# PCD.net
KiCad netlist of a schematic drawn in EAGLE
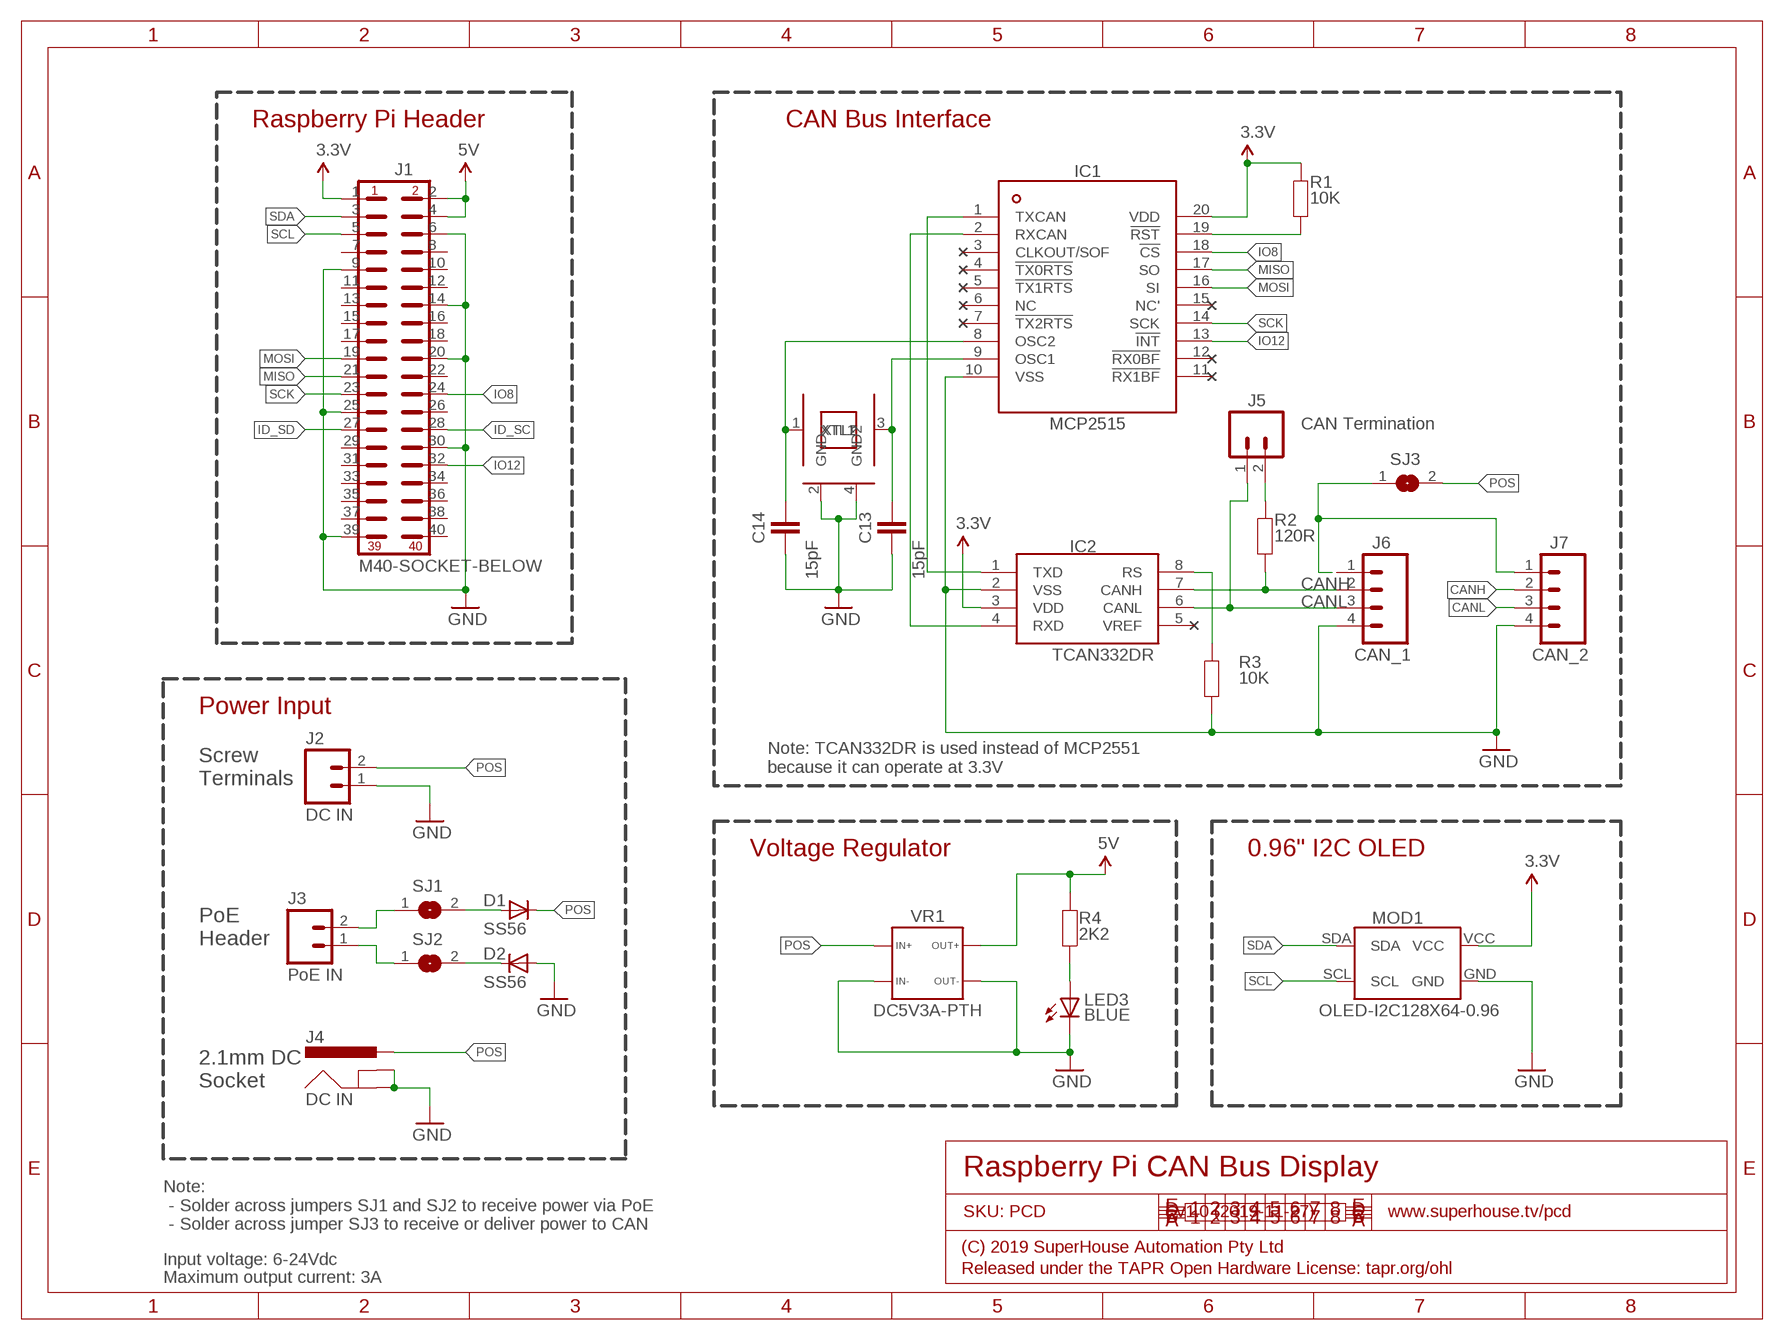
[diagram p0: schematic, sheet 1]

(export (version "E")
  (design (tool "Eeschema 10.0.6"))
  (components
    (comp (ref "C13")
      (value "15pF")
      (footprint "eagle-import:C0603")
      (libsource (lib "eagle-import") (part "CAP0603"))
    )
    (comp (ref "C14")
      (value "15pF")
      (footprint "eagle-import:C0603")
      (libsource (lib "eagle-import") (part "CAP0603"))
    )
    (comp (ref "D1")
      (value "SS56")
      (footprint "eagle-import:SMA-DIODE")
      (libsource (lib "eagle-import") (part "DIODESMA"))
    )
    (comp (ref "D2")
      (value "SS56")
      (footprint "eagle-import:SMA-DIODE")
      (libsource (lib "eagle-import") (part "DIODESMA"))
    )
    (comp (ref "IC1")
      (value "MCP2515")
      (footprint "eagle-import:TSSOP20")
      (libsource (lib "eagle-import") (part "MCP2515"))
    )
    (comp (ref "IC2")
      (value "TCAN332DR")
      (footprint "eagle-import:SO08")
      (libsource (lib "eagle-import") (part "MCP2551"))
    )
    (comp (ref "J1")
      (value "M40-SOCKET-BELOW")
      (footprint "eagle-import:2X20-S-BELOW")
      (libsource (lib "eagle-import") (part "M40-SOCKET-BELOW"))
    )
    (comp (ref "J2")
      (value "DC IN")
      (footprint "eagle-import:SCREWTERMINAL-3.5MM-2")
      (libsource (lib "eagle-import") (part "M02-SCREW-3.5MM"))
    )
    (comp (ref "J3")
      (value "PoE IN")
      (footprint "eagle-import:1X02-S-BELOW")
      (libsource (lib "eagle-import") (part "M02-SOCKET-BELOW"))
    )
    (comp (ref "J4")
      (value "DC IN")
      (footprint "eagle-import:POWER_JACK_SLOTS")
      (libsource (lib "eagle-import") (part "POWER_JACK-SLOTS"))
    )
    (comp (ref "J5")
      (value "CAN Termination")
      (footprint "eagle-import:1X02-P")
      (libsource (lib "eagle-import") (part "M02-PIN"))
    )
    (comp (ref "J6")
      (value "CAN_1")
      (footprint "eagle-import:1X04-P")
      (libsource (lib "eagle-import") (part "M04-PIN"))
    )
    (comp (ref "J7")
      (value "CAN_2")
      (footprint "eagle-import:1X04-P")
      (libsource (lib "eagle-import") (part "M04-PIN"))
    )
    (comp (ref "LED3")
      (value "BLUE")
      (footprint "eagle-import:LED-0603")
      (libsource (lib "eagle-import") (part "LED0603"))
    )
    (comp (ref "MOD1")
      (value "OLED-I2C128X64-0.96")
      (footprint "eagle-import:OLED-128X64-0.96")
      (libsource (lib "eagle-import") (part "OLED-I2C128X64-0.96"))
    )
    (comp (ref "R1")
      (value "10K")
      (footprint "eagle-import:R0603")
      (libsource (lib "eagle-import") (part "RESISTOR0603"))
    )
    (comp (ref "R2")
      (value "120R")
      (footprint "eagle-import:R0603")
      (libsource (lib "eagle-import") (part "RESISTOR0603"))
    )
    (comp (ref "R3")
      (value "10K")
      (footprint "eagle-import:R0603")
      (libsource (lib "eagle-import") (part "RESISTOR0603"))
    )
    (comp (ref "R4")
      (value "2K2")
      (footprint "eagle-import:R0603")
      (libsource (lib "eagle-import") (part "RESISTOR0603"))
    )
    (comp (ref "SJ1")
      (value "SJN")
      (footprint "eagle-import:SJ")
      (libsource (lib "eagle-import") (part "SJN"))
    )
    (comp (ref "SJ2")
      (value "SJN")
      (footprint "eagle-import:SJ")
      (libsource (lib "eagle-import") (part "SJN"))
    )
    (comp (ref "SJ3")
      (value "SJN")
      (footprint "eagle-import:SJ")
      (libsource (lib "eagle-import") (part "SJN"))
    )
    (comp (ref "VR1")
      (value "DC5V3A-PTH")
      (footprint "eagle-import:DC5V3A-PTH")
      (libsource (lib "eagle-import") (part "DC5V3A-PTH"))
    )
    (comp (ref "XTL3")
      (value "16MHz")
      (footprint "eagle-import:CRYSTAL-SMD-3X2")
      (libsource (lib "eagle-import") (part "CRYSTAL-GND3X2"))
    )
  )
  (nets
    (net (code "1") (name "3.3V") (class "Default")
      (node (ref "IC1") (pin "20") (pinfunction "VDD_20") (pintype "bidirectional"))
      (node (ref "IC2") (pin "3") (pinfunction "VDD_3") (pintype "bidirectional"))
      (node (ref "J1") (pin "1") (pinfunction "1_1") (pintype "passive"))
      (node (ref "MOD1") (pin "VCC") (pinfunction "VCC_VCC") (pintype "bidirectional"))
      (node (ref "R1") (pin "2") (pinfunction "2_2") (pintype "passive"))
    )
    (net (code "2") (name "5V") (class "Default")
      (node (ref "J1") (pin "2") (pinfunction "2_2") (pintype "passive"))
      (node (ref "J1") (pin "4") (pinfunction "4_4") (pintype "passive"))
      (node (ref "R4") (pin "1") (pinfunction "1_1") (pintype "passive"))
      (node (ref "VR1") (pin "3A") (pinfunction "3_3A") (pintype "bidirectional"))
      (node (ref "VR1") (pin "3B") (pinfunction "3_3B") (pintype "bidirectional"))
    )
    (net (code "3") (name "CANH") (class "Default")
      (node (ref "IC2") (pin "7") (pinfunction "CANH_7") (pintype "bidirectional"))
      (node (ref "J6") (pin "2") (pinfunction "2_2") (pintype "passive"))
      (node (ref "J7") (pin "2") (pinfunction "2_2") (pintype "passive"))
      (node (ref "R2") (pin "1") (pinfunction "1_1") (pintype "passive"))
    )
    (net (code "4") (name "CANL") (class "Default")
      (node (ref "IC2") (pin "6") (pinfunction "CANL_6") (pintype "bidirectional"))
      (node (ref "J5") (pin "1") (pinfunction "1_1") (pintype "passive"))
      (node (ref "J6") (pin "3") (pinfunction "3_3") (pintype "passive"))
      (node (ref "J7") (pin "3") (pinfunction "3_3") (pintype "passive"))
    )
    (net (code "5") (name "GND") (class "Default")
      (node (ref "C13") (pin "1") (pinfunction "1_1") (pintype "passive"))
      (node (ref "C14") (pin "1") (pinfunction "1_1") (pintype "passive"))
      (node (ref "D2") (pin "A") (pinfunction "A_A") (pintype "passive"))
      (node (ref "IC1") (pin "10") (pinfunction "VSS_10") (pintype "bidirectional"))
      (node (ref "IC2") (pin "2") (pinfunction "VSS_2") (pintype "bidirectional"))
      (node (ref "J1") (pin "14") (pinfunction "14_14") (pintype "passive"))
      (node (ref "J1") (pin "20") (pinfunction "20_20") (pintype "passive"))
      (node (ref "J1") (pin "25") (pinfunction "25_25") (pintype "passive"))
      (node (ref "J1") (pin "30") (pinfunction "30_30") (pintype "passive"))
      (node (ref "J1") (pin "39") (pinfunction "39_39") (pintype "passive"))
      (node (ref "J1") (pin "6") (pinfunction "6_6") (pintype "passive"))
      (node (ref "J1") (pin "9") (pinfunction "9_9") (pintype "passive"))
      (node (ref "J2") (pin "1") (pinfunction "1_1") (pintype "passive"))
      (node (ref "J4") (pin "GND") (pinfunction "GND_GND") (pintype "bidirectional"))
      (node (ref "J4") (pin "GNDBREAK") (pinfunction "GNDBREAK_GNDBREAK") (pintype "bidirectional"))
      (node (ref "J6") (pin "4") (pinfunction "4_4") (pintype "passive"))
      (node (ref "J7") (pin "4") (pinfunction "4_4") (pintype "passive"))
      (node (ref "LED3") (pin "C") (pinfunction "C_C") (pintype "passive"))
      (node (ref "MOD1") (pin "GND") (pinfunction "GND_GND") (pintype "bidirectional"))
      (node (ref "R3") (pin "1") (pinfunction "1_1") (pintype "passive"))
      (node (ref "VR1") (pin "1A") (pinfunction "1_1A") (pintype "bidirectional"))
      (node (ref "VR1") (pin "1B") (pinfunction "1_1B") (pintype "bidirectional"))
      (node (ref "VR1") (pin "4A") (pinfunction "4_4A") (pintype "bidirectional"))
      (node (ref "VR1") (pin "4B") (pinfunction "4_4B") (pintype "bidirectional"))
      (node (ref "XTL3") (pin "2") (pinfunction "GND_2") (pintype "bidirectional"))
      (node (ref "XTL3") (pin "4") (pinfunction "GND2_4") (pintype "bidirectional"))
    )
    (net (code "6") (name "ID_SC") (class "Default")
      (node (ref "J1") (pin "28") (pinfunction "28_28") (pintype "passive"))
    )
    (net (code "7") (name "ID_SD") (class "Default")
      (node (ref "J1") (pin "27") (pinfunction "27_27") (pintype "passive"))
    )
    (net (code "8") (name "IO8") (class "Default")
      (node (ref "IC1") (pin "18") (pinfunction "~{CS}_18") (pintype "bidirectional"))
      (node (ref "J1") (pin "24") (pinfunction "24_24") (pintype "passive"))
    )
    (net (code "9") (name "IO12") (class "Default")
      (node (ref "IC1") (pin "13") (pinfunction "~{INT}_13") (pintype "bidirectional"))
      (node (ref "J1") (pin "32") (pinfunction "32_32") (pintype "passive"))
    )
    (net (code "10") (name "MISO") (class "Default")
      (node (ref "IC1") (pin "17") (pinfunction "SO_17") (pintype "bidirectional"))
      (node (ref "J1") (pin "21") (pinfunction "21_21") (pintype "passive"))
    )
    (net (code "11") (name "MOSI") (class "Default")
      (node (ref "IC1") (pin "16") (pinfunction "SI_16") (pintype "bidirectional"))
      (node (ref "J1") (pin "19") (pinfunction "19_19") (pintype "passive"))
    )
    (net (code "12") (name "Net-(D1-PadA)") (class "Default")
      (node (ref "D1") (pin "A") (pinfunction "A_A") (pintype "passive"))
      (node (ref "SJ1") (pin "2") (pinfunction "2_2") (pintype "passive"))
    )
    (net (code "13") (name "Net-(D2-PadC)") (class "Default")
      (node (ref "D2") (pin "C") (pinfunction "C_C") (pintype "passive"))
      (node (ref "SJ2") (pin "2") (pinfunction "2_2") (pintype "passive"))
    )
    (net (code "14") (name "Net-(IC1-OSC1)") (class "Default")
      (node (ref "C13") (pin "2") (pinfunction "2_2") (pintype "passive"))
      (node (ref "IC1") (pin "9") (pinfunction "OSC1_9") (pintype "bidirectional"))
      (node (ref "XTL3") (pin "3") (pinfunction "XTL2_3") (pintype "bidirectional"))
    )
    (net (code "15") (name "Net-(IC1-OSC2)") (class "Default")
      (node (ref "C14") (pin "2") (pinfunction "2_2") (pintype "passive"))
      (node (ref "IC1") (pin "8") (pinfunction "OSC2_8") (pintype "bidirectional"))
      (node (ref "XTL3") (pin "1") (pinfunction "XTL1_1") (pintype "bidirectional"))
    )
    (net (code "16") (name "Net-(IC1-RXCAN)") (class "Default")
      (node (ref "IC1") (pin "2") (pinfunction "RXCAN_2") (pintype "bidirectional"))
      (node (ref "IC2") (pin "4") (pinfunction "RXD_4") (pintype "bidirectional"))
    )
    (net (code "17") (name "Net-(IC1-TXCAN)") (class "Default")
      (node (ref "IC1") (pin "1") (pinfunction "TXCAN_1") (pintype "bidirectional"))
      (node (ref "IC2") (pin "1") (pinfunction "TXD_1") (pintype "bidirectional"))
    )
    (net (code "18") (name "Net-(IC1-~{RST})") (class "Default")
      (node (ref "IC1") (pin "19") (pinfunction "~{RST}_19") (pintype "bidirectional"))
      (node (ref "R1") (pin "1") (pinfunction "1_1") (pintype "passive"))
    )
    (net (code "19") (name "Net-(IC2-RS)") (class "Default")
      (node (ref "IC2") (pin "8") (pinfunction "RS_8") (pintype "bidirectional"))
      (node (ref "R3") (pin "2") (pinfunction "2_2") (pintype "passive"))
    )
    (net (code "20") (name "Net-(J3-Pad1)") (class "Default")
      (node (ref "J3") (pin "1") (pinfunction "1_1") (pintype "passive"))
      (node (ref "SJ2") (pin "1") (pinfunction "1_1") (pintype "passive"))
    )
    (net (code "21") (name "Net-(J3-Pad2)") (class "Default")
      (node (ref "J3") (pin "2") (pinfunction "2_2") (pintype "passive"))
      (node (ref "SJ1") (pin "1") (pinfunction "1_1") (pintype "passive"))
    )
    (net (code "22") (name "Net-(J5-Pad2)") (class "Default")
      (node (ref "J5") (pin "2") (pinfunction "2_2") (pintype "passive"))
      (node (ref "R2") (pin "2") (pinfunction "2_2") (pintype "passive"))
    )
    (net (code "23") (name "Net-(J6-Pad1)") (class "Default")
      (node (ref "J6") (pin "1") (pinfunction "1_1") (pintype "passive"))
      (node (ref "J7") (pin "1") (pinfunction "1_1") (pintype "passive"))
      (node (ref "SJ3") (pin "1") (pinfunction "1_1") (pintype "passive"))
    )
    (net (code "24") (name "Net-(LED3-PadA)") (class "Default")
      (node (ref "LED3") (pin "A") (pinfunction "A_A") (pintype "passive"))
      (node (ref "R4") (pin "2") (pinfunction "2_2") (pintype "passive"))
    )
    (net (code "25") (name "POS") (class "Default")
      (node (ref "D1") (pin "C") (pinfunction "C_C") (pintype "passive"))
      (node (ref "J2") (pin "2") (pinfunction "2_2") (pintype "passive"))
      (node (ref "J4") (pin "PWR") (pinfunction "PWR_PWR") (pintype "bidirectional"))
      (node (ref "SJ3") (pin "2") (pinfunction "2_2") (pintype "passive"))
      (node (ref "VR1") (pin "2A") (pinfunction "2_2A") (pintype "bidirectional"))
      (node (ref "VR1") (pin "2B") (pinfunction "2_2B") (pintype "bidirectional"))
    )
    (net (code "26") (name "SCK") (class "Default")
      (node (ref "IC1") (pin "14") (pinfunction "SCK_14") (pintype "bidirectional"))
      (node (ref "J1") (pin "23") (pinfunction "23_23") (pintype "passive"))
    )
    (net (code "27") (name "SCL") (class "Default")
      (node (ref "J1") (pin "5") (pinfunction "5_5") (pintype "passive"))
      (node (ref "MOD1") (pin "SCL") (pinfunction "SCL_SCL") (pintype "bidirectional"))
    )
    (net (code "28") (name "SDA") (class "Default")
      (node (ref "J1") (pin "3") (pinfunction "3_3") (pintype "passive"))
      (node (ref "MOD1") (pin "SDA") (pinfunction "SDA_SDA") (pintype "bidirectional"))
    )
    (net (code "29") (name "unconnected-(IC1-CLKOUT{slash}SOF-Pad3)") (class "Default")
      (node (ref "IC1") (pin "3") (pinfunction "CLKOUT/SOF_3") (pintype "bidirectional"))
    )
    (net (code "30") (name "unconnected-(IC1-NC'-Pad15)") (class "Default")
      (node (ref "IC1") (pin "15") (pinfunction "NC'_15") (pintype "bidirectional"))
    )
    (net (code "31") (name "unconnected-(IC1-NC-Pad6)") (class "Default")
      (node (ref "IC1") (pin "6") (pinfunction "NC_6") (pintype "bidirectional"))
    )
    (net (code "32") (name "unconnected-(IC1-~{RX0BF}-Pad12)") (class "Default")
      (node (ref "IC1") (pin "12") (pinfunction "~{RX0BF}_12") (pintype "bidirectional"))
    )
    (net (code "33") (name "unconnected-(IC1-~{RX1BF}-Pad11)") (class "Default")
      (node (ref "IC1") (pin "11") (pinfunction "~{RX1BF}_11") (pintype "bidirectional"))
    )
    (net (code "34") (name "unconnected-(IC1-~{TX0RTS}-Pad4)") (class "Default")
      (node (ref "IC1") (pin "4") (pinfunction "~{TX0RTS}_4") (pintype "bidirectional"))
    )
    (net (code "35") (name "unconnected-(IC1-~{TX1RTS}-Pad5)") (class "Default")
      (node (ref "IC1") (pin "5") (pinfunction "~{TX1RTS}_5") (pintype "bidirectional"))
    )
    (net (code "36") (name "unconnected-(IC1-~{TX2RTS}-Pad7)") (class "Default")
      (node (ref "IC1") (pin "7") (pinfunction "~{TX2RTS}_7") (pintype "bidirectional"))
    )
    (net (code "37") (name "unconnected-(IC2-VREF-Pad5)") (class "Default")
      (node (ref "IC2") (pin "5") (pinfunction "VREF_5") (pintype "bidirectional"))
    )
    (net (code "38") (name "unconnected-(J1-Pad7)") (class "Default")
      (node (ref "J1") (pin "7") (pinfunction "7_7") (pintype "passive"))
    )
    (net (code "39") (name "unconnected-(J1-Pad8)") (class "Default")
      (node (ref "J1") (pin "8") (pinfunction "8_8") (pintype "passive"))
    )
    (net (code "40") (name "unconnected-(J1-Pad10)") (class "Default")
      (node (ref "J1") (pin "10") (pinfunction "10_10") (pintype "passive"))
    )
    (net (code "41") (name "unconnected-(J1-Pad11)") (class "Default")
      (node (ref "J1") (pin "11") (pinfunction "11_11") (pintype "passive"))
    )
    (net (code "42") (name "unconnected-(J1-Pad12)") (class "Default")
      (node (ref "J1") (pin "12") (pinfunction "12_12") (pintype "passive"))
    )
    (net (code "43") (name "unconnected-(J1-Pad13)") (class "Default")
      (node (ref "J1") (pin "13") (pinfunction "13_13") (pintype "passive"))
    )
    (net (code "44") (name "unconnected-(J1-Pad15)") (class "Default")
      (node (ref "J1") (pin "15") (pinfunction "15_15") (pintype "passive"))
    )
    (net (code "45") (name "unconnected-(J1-Pad16)") (class "Default")
      (node (ref "J1") (pin "16") (pinfunction "16_16") (pintype "passive"))
    )
    (net (code "46") (name "unconnected-(J1-Pad17)") (class "Default")
      (node (ref "J1") (pin "17") (pinfunction "17_17") (pintype "passive"))
    )
    (net (code "47") (name "unconnected-(J1-Pad18)") (class "Default")
      (node (ref "J1") (pin "18") (pinfunction "18_18") (pintype "passive"))
    )
    (net (code "48") (name "unconnected-(J1-Pad22)") (class "Default")
      (node (ref "J1") (pin "22") (pinfunction "22_22") (pintype "passive"))
    )
    (net (code "49") (name "unconnected-(J1-Pad26)") (class "Default")
      (node (ref "J1") (pin "26") (pinfunction "26_26") (pintype "passive"))
    )
    (net (code "50") (name "unconnected-(J1-Pad29)") (class "Default")
      (node (ref "J1") (pin "29") (pinfunction "29_29") (pintype "passive"))
    )
    (net (code "51") (name "unconnected-(J1-Pad31)") (class "Default")
      (node (ref "J1") (pin "31") (pinfunction "31_31") (pintype "passive"))
    )
    (net (code "52") (name "unconnected-(J1-Pad33)") (class "Default")
      (node (ref "J1") (pin "33") (pinfunction "33_33") (pintype "passive"))
    )
    (net (code "53") (name "unconnected-(J1-Pad34)") (class "Default")
      (node (ref "J1") (pin "34") (pinfunction "34_34") (pintype "passive"))
    )
    (net (code "54") (name "unconnected-(J1-Pad35)") (class "Default")
      (node (ref "J1") (pin "35") (pinfunction "35_35") (pintype "passive"))
    )
    (net (code "55") (name "unconnected-(J1-Pad36)") (class "Default")
      (node (ref "J1") (pin "36") (pinfunction "36_36") (pintype "passive"))
    )
    (net (code "56") (name "unconnected-(J1-Pad37)") (class "Default")
      (node (ref "J1") (pin "37") (pinfunction "37_37") (pintype "passive"))
    )
    (net (code "57") (name "unconnected-(J1-Pad38)") (class "Default")
      (node (ref "J1") (pin "38") (pinfunction "38_38") (pintype "passive"))
    )
    (net (code "58") (name "unconnected-(J1-Pad40)") (class "Default")
      (node (ref "J1") (pin "40") (pinfunction "40_40") (pintype "passive"))
    )
  )
)
